# connectors_and_power.net
KiCad netlist of a schematic drawn in Altium Designer
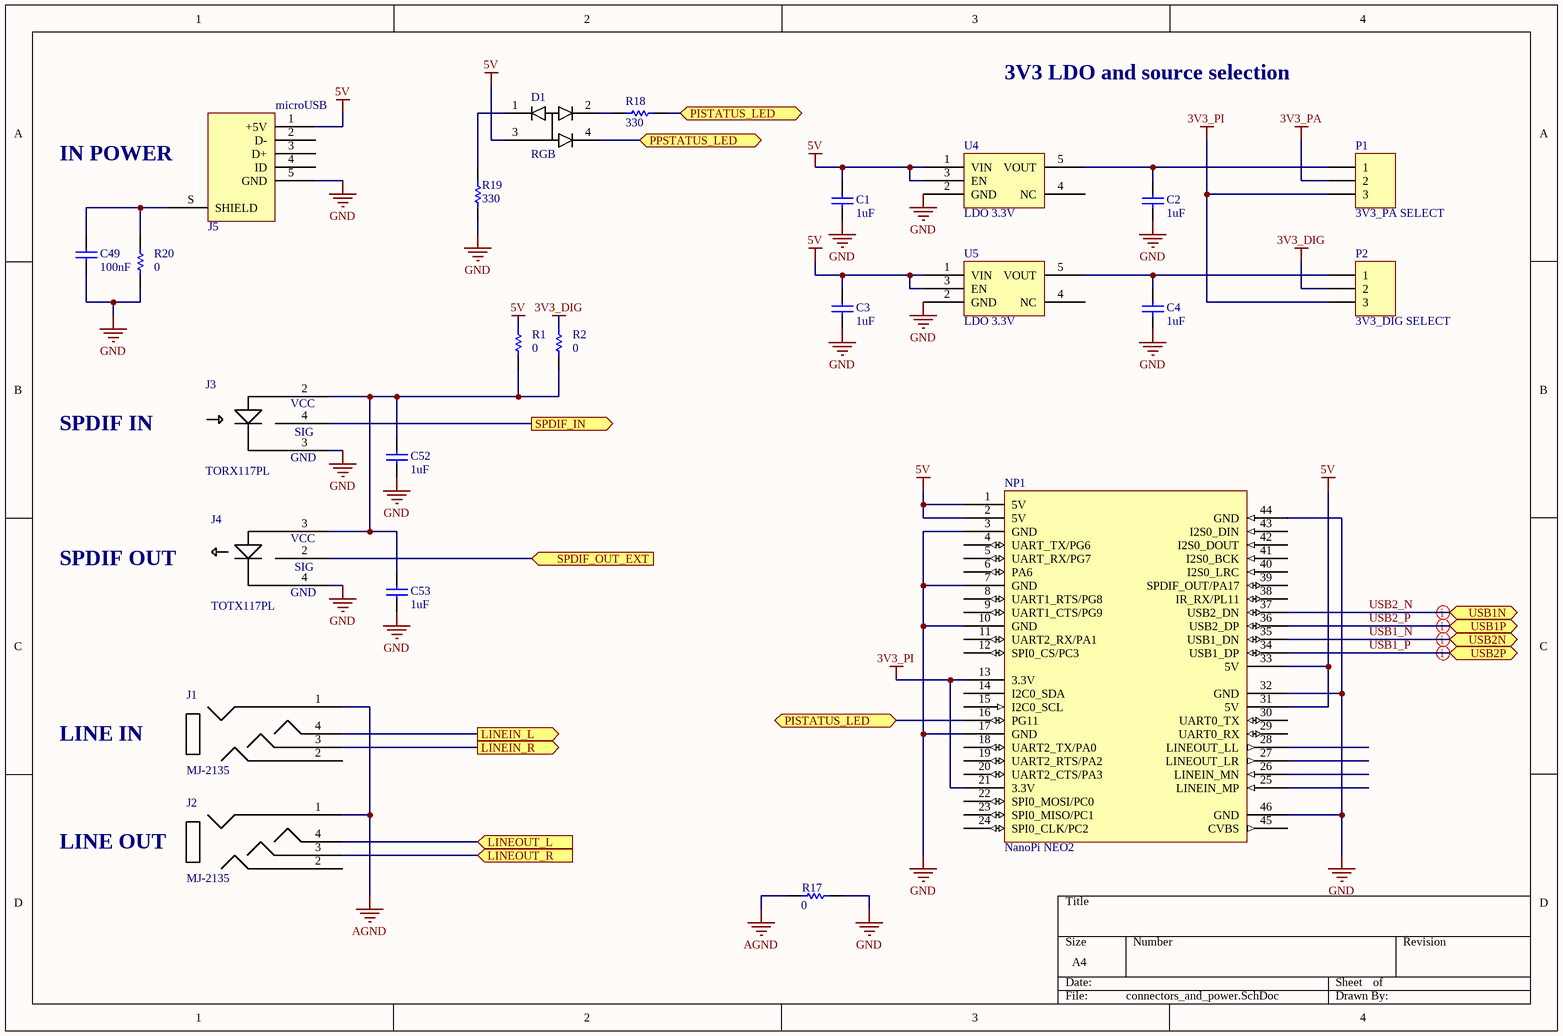
[diagram p0: connectors_and_power.SchDoc]

(export (version "E")
  (design (tool "Eeschema 10.0.6"))
  (components
    (comp (ref "C1")
      (value "1uF")
      (footprint "C_0402")
      (libsource (lib "Miscellaneous Devices") (part "Cap"))
    )
    (comp (ref "C2")
      (value "1uF")
      (footprint "C_0402")
      (libsource (lib "Miscellaneous Devices") (part "Cap"))
    )
    (comp (ref "C3")
      (value "1uF")
      (footprint "C_0402")
      (libsource (lib "Miscellaneous Devices") (part "Cap"))
    )
    (comp (ref "C4")
      (value "1uF")
      (footprint "C_0402")
      (libsource (lib "Miscellaneous Devices") (part "Cap"))
    )
    (comp (ref "C49")
      (value "100nF")
      (footprint "C_0402")
      (libsource (lib "Miscellaneous Devices") (part "Cap"))
    )
    (comp (ref "C52")
      (value "1uF")
      (footprint "C_0402")
      (libsource (lib "Miscellaneous Devices") (part "Cap"))
    )
    (comp (ref "C53")
      (value "1uF")
      (footprint "C_0402")
      (libsource (lib "Miscellaneous Devices") (part "Cap"))
    )
    (comp (ref "D1") (value "RGB") (footprint "RGB") (libsource (lib "Active Components") (part "RGB")))
    (comp (ref "J1")
      (value "MJ-2135")
      (footprint "audio jack")
      (description "3.5mm Audio jack")
      (libsource (lib "Connectors") (part "MJ-2135"))
    )
    (comp (ref "J2")
      (value "MJ-2135")
      (footprint "audio jack")
      (description "3.5mm Audio jack")
      (libsource (lib "Connectors") (part "MJ-2135"))
    )
    (comp (ref "J3")
      (value "TORX117PL")
      (footprint "TOXX177PL")
      (libsource (lib "Connectors") (part "TORX117PL"))
    )
    (comp (ref "J4")
      (value "TOTX117PL")
      (footprint "TOXX177PL")
      (libsource (lib "Connectors") (part "TOTX117PL"))
    )
    (comp (ref "J5")
      (value "Micro USB Jack")
      (footprint "microUSB")
      (description "Molex micro USB AB  47589-0001")
      (libsource (lib "Connectors") (part "Micro USB Jack"))
    )
    (comp (ref "NP1")
      (value "nanopi_neo2")
      (footprint "nanopi_neo2_dock")
      (description "Flipped NanoPi NEO2 dock")
      (libsource (lib "project_specific") (part "nanopi_neo2"))
    )
    (comp (ref "P1")
      (value "3V3_PA SELECT")
      (footprint "HDR1X3")
      (description "Header, 3-Pin")
      (fields (field (name "PUBLISHER") "Altium Limited"))
      (libsource (lib "Miscellaneous Connectors") (part "Header 3"))
    )
    (comp (ref "P2")
      (value "3V3_DIG SELECT")
      (footprint "HDR1X3")
      (description "Header, 3-Pin")
      (fields (field (name "PUBLISHER") "Altium Limited"))
      (libsource (lib "Miscellaneous Connectors") (part "Header 3"))
    )
    (comp (ref "R1")
      (value "0")
      (footprint "R_0402")
      (description "Resistor")
      (fields (field (name "Comment") "Res1"))
      (libsource (lib "Miscellaneous Devices") (part "Res1"))
    )
    (comp (ref "R2")
      (value "0")
      (footprint "R_0402")
      (description "Resistor")
      (fields (field (name "Comment") "Res1"))
      (libsource (lib "Miscellaneous Devices") (part "Res1"))
    )
    (comp (ref "R17")
      (value "0")
      (footprint "R_0402")
      (description "Resistor")
      (fields (field (name "Comment") "Res1"))
      (libsource (lib "Miscellaneous Devices") (part "Res1"))
    )
    (comp (ref "R18")
      (value "Res1")
      (footprint "R_0402")
      (description "Resistor")
      (fields (field (name "ALTIUM_UNNAMED_1") "330"))
      (libsource (lib "Miscellaneous Devices") (part "Res1"))
    )
    (comp (ref "R19")
      (value "Res1")
      (footprint "R_0402")
      (description "Resistor")
      (fields (field (name "ALTIUM_UNNAMED_1") "330"))
      (libsource (lib "Miscellaneous Devices") (part "Res1"))
    )
    (comp (ref "R20")
      (value "0")
      (footprint "R_0402")
      (description "Resistor")
      (fields (field (name "Comment") "Res1"))
      (libsource (lib "Miscellaneous Devices") (part "Res1"))
    )
    (comp (ref "U4")
      (value "LDO 3.3V")
      (footprint "SOT95P280X145-5N")
      (libsource (lib "Active Components") (part "LDO 3.3V"))
    )
    (comp (ref "U5")
      (value "LDO 3.3V")
      (footprint "SOT95P280X145-5N")
      (libsource (lib "Active Components") (part "LDO 3.3V"))
    )
  )
  (nets
    (net (code "1") (name "/LINEIN_L") (class "Default")
      (node (ref "J1") (pin "4") (pinfunction "4_4") (pintype "passive"))
    )
    (net (code "2") (name "/LINEIN_R") (class "Default")
      (node (ref "J1") (pin "3") (pinfunction "3_3") (pintype "passive"))
    )
    (net (code "3") (name "/LINEOUT_L") (class "Default")
      (node (ref "J2") (pin "4") (pinfunction "4_4") (pintype "passive"))
    )
    (net (code "4") (name "/LINEOUT_R") (class "Default")
      (node (ref "J2") (pin "3") (pinfunction "3_3") (pintype "passive"))
    )
    (net (code "5") (name "/PISTATUS_LED") (class "Default")
      (node (ref "NP1") (pin "16") (pinfunction "PG11_16") (pintype "bidirectional"))
      (node (ref "R18") (pin "1") (pinfunction "1_1") (pintype "passive"))
    )
    (net (code "6") (name "/PPSTATUS_LED") (class "Default")
      (node (ref "D1") (pin "4") (pinfunction "BLUE_4") (pintype "passive"))
    )
    (net (code "7") (name "/SPDIF_IN") (class "Default")
      (node (ref "J3") (pin "4") (pinfunction "SIG_4") (pintype "passive"))
    )
    (net (code "8") (name "/SPDIF_OUT_EXT") (class "Default")
      (node (ref "J4") (pin "2") (pinfunction "SIG_2") (pintype "passive"))
    )
    (net (code "9") (name "/USB1_N") (class "Default")
      (node (ref "NP1") (pin "35") (pinfunction "USB1_DN_35") (pintype "bidirectional"))
    )
    (net (code "10") (name "/USB1_P") (class "Default")
      (node (ref "NP1") (pin "34") (pinfunction "USB1_DP_34") (pintype "bidirectional"))
    )
    (net (code "11") (name "/USB2_N") (class "Default")
      (node (ref "NP1") (pin "37") (pinfunction "USB2_DN_37") (pintype "bidirectional"))
    )
    (net (code "12") (name "/USB2_P") (class "Default")
      (node (ref "NP1") (pin "36") (pinfunction "USB2_DP_36") (pintype "bidirectional"))
    )
    (net (code "13") (name "3V3_DIG") (class "Default")
      (node (ref "P2") (pin "2") (pinfunction "2_2") (pintype "passive"))
      (node (ref "R2") (pin "2") (pinfunction "2_2") (pintype "passive"))
    )
    (net (code "14") (name "3V3_PA") (class "Default")
      (node (ref "P1") (pin "2") (pinfunction "2_2") (pintype "passive"))
    )
    (net (code "15") (name "3V3_PI") (class "Default")
      (node (ref "NP1") (pin "13") (pinfunction "3.3V_13") (pintype "power_in"))
      (node (ref "NP1") (pin "21") (pinfunction "3.3V_21") (pintype "power_in"))
      (node (ref "P1") (pin "3") (pinfunction "3_3") (pintype "passive"))
      (node (ref "P2") (pin "3") (pinfunction "3_3") (pintype "passive"))
    )
    (net (code "16") (name "5V") (class "Default")
      (node (ref "C1") (pin "2") (pinfunction "2_2") (pintype "passive"))
      (node (ref "C3") (pin "2") (pinfunction "2_2") (pintype "passive"))
      (node (ref "D1") (pin "3") (pinfunction "ANODE_3") (pintype "passive"))
      (node (ref "J5") (pin "1") (pinfunction "+5V_1") (pintype "passive"))
      (node (ref "NP1") (pin "1") (pinfunction "5V_1") (pintype "power_in"))
      (node (ref "NP1") (pin "2") (pinfunction "5V_2") (pintype "power_in"))
      (node (ref "NP1") (pin "31") (pinfunction "5V_31") (pintype "power_in"))
      (node (ref "NP1") (pin "33") (pinfunction "5V_33") (pintype "power_in"))
      (node (ref "R1") (pin "2") (pinfunction "2_2") (pintype "passive"))
      (node (ref "U4") (pin "1") (pinfunction "VIN_1") (pintype "passive"))
      (node (ref "U4") (pin "3") (pinfunction "EN_3") (pintype "passive"))
      (node (ref "U5") (pin "1") (pinfunction "VIN_1") (pintype "passive"))
      (node (ref "U5") (pin "3") (pinfunction "EN_3") (pintype "passive"))
    )
    (net (code "17") (name "AGND") (class "Default")
      (node (ref "J1") (pin "1") (pinfunction "1_1") (pintype "passive"))
      (node (ref "J2") (pin "1") (pinfunction "1_1") (pintype "passive"))
      (node (ref "R17") (pin "2") (pinfunction "2_2") (pintype "passive"))
    )
    (net (code "18") (name "GND") (class "Default")
      (node (ref "C1") (pin "1") (pinfunction "1_1") (pintype "passive"))
      (node (ref "C2") (pin "1") (pinfunction "1_1") (pintype "passive"))
      (node (ref "C3") (pin "1") (pinfunction "1_1") (pintype "passive"))
      (node (ref "C4") (pin "1") (pinfunction "1_1") (pintype "passive"))
      (node (ref "C49") (pin "1") (pinfunction "1_1") (pintype "passive"))
      (node (ref "C52") (pin "1") (pinfunction "1_1") (pintype "passive"))
      (node (ref "C53") (pin "1") (pinfunction "1_1") (pintype "passive"))
      (node (ref "J3") (pin "3") (pinfunction "GND_3") (pintype "passive"))
      (node (ref "J4") (pin "4") (pinfunction "GND_4") (pintype "passive"))
      (node (ref "J5") (pin "5") (pinfunction "GND_5") (pintype "passive"))
      (node (ref "NP1") (pin "10") (pinfunction "GND_10") (pintype "power_in"))
      (node (ref "NP1") (pin "17") (pinfunction "GND_17") (pintype "power_in"))
      (node (ref "NP1") (pin "3") (pinfunction "GND_3") (pintype "power_in"))
      (node (ref "NP1") (pin "32") (pinfunction "GND_32") (pintype "power_in"))
      (node (ref "NP1") (pin "44") (pinfunction "GND_44") (pintype "input"))
      (node (ref "NP1") (pin "46") (pinfunction "GND_46") (pintype "power_in"))
      (node (ref "NP1") (pin "7") (pinfunction "GND_7") (pintype "power_in"))
      (node (ref "R17") (pin "1") (pinfunction "1_1") (pintype "passive"))
      (node (ref "R19") (pin "1") (pinfunction "1_1") (pintype "passive"))
      (node (ref "R20") (pin "1") (pinfunction "1_1") (pintype "passive"))
      (node (ref "U4") (pin "2") (pinfunction "GND_2") (pintype "passive"))
      (node (ref "U5") (pin "2") (pinfunction "GND_2") (pintype "passive"))
    )
    (net (code "19") (name "Net-(D1-GREEN)") (class "Default")
      (node (ref "D1") (pin "2") (pinfunction "GREEN_2") (pintype "passive"))
      (node (ref "R18") (pin "2") (pinfunction "2_2") (pintype "passive"))
    )
    (net (code "20") (name "Net-(D1-RED)") (class "Default")
      (node (ref "D1") (pin "1") (pinfunction "RED_1") (pintype "passive"))
      (node (ref "R19") (pin "2") (pinfunction "2_2") (pintype "passive"))
    )
    (net (code "21") (name "Net-(J3-VCC)") (class "Default")
      (node (ref "C52") (pin "2") (pinfunction "2_2") (pintype "passive"))
      (node (ref "C53") (pin "2") (pinfunction "2_2") (pintype "passive"))
      (node (ref "J3") (pin "2") (pinfunction "VCC_2") (pintype "passive"))
      (node (ref "J4") (pin "3") (pinfunction "VCC_3") (pintype "passive"))
      (node (ref "R1") (pin "1") (pinfunction "1_1") (pintype "passive"))
      (node (ref "R2") (pin "1") (pinfunction "1_1") (pintype "passive"))
    )
    (net (code "22") (name "Net-(J5-SHIELD)") (class "Default")
      (node (ref "C49") (pin "2") (pinfunction "2_2") (pintype "passive"))
      (node (ref "J5") (pin "S") (pinfunction "SHIELD_S") (pintype "passive"))
      (node (ref "R20") (pin "2") (pinfunction "2_2") (pintype "passive"))
    )
    (net (code "23") (name "Net-(U4-VOUT)") (class "Default")
      (node (ref "C2") (pin "2") (pinfunction "2_2") (pintype "passive"))
      (node (ref "P1") (pin "1") (pinfunction "1_1") (pintype "passive"))
      (node (ref "U4") (pin "5") (pinfunction "VOUT_5") (pintype "passive"))
    )
    (net (code "24") (name "Net-(U5-VOUT)") (class "Default")
      (node (ref "C4") (pin "2") (pinfunction "2_2") (pintype "passive"))
      (node (ref "P2") (pin "1") (pinfunction "1_1") (pintype "passive"))
      (node (ref "U5") (pin "5") (pinfunction "VOUT_5") (pintype "passive"))
    )
    (net (code "25") (name "unconnected-(J1-Pad2)") (class "Default")
      (node (ref "J1") (pin "2") (pinfunction "2_2") (pintype "passive"))
    )
    (net (code "26") (name "unconnected-(J2-Pad2)") (class "Default")
      (node (ref "J2") (pin "2") (pinfunction "2_2") (pintype "passive"))
    )
    (net (code "27") (name "unconnected-(J5-D+-Pad3)") (class "Default")
      (node (ref "J5") (pin "3") (pinfunction "D+_3") (pintype "passive"))
    )
    (net (code "28") (name "unconnected-(J5-D--Pad2)") (class "Default")
      (node (ref "J5") (pin "2") (pinfunction "D-_2") (pintype "passive"))
    )
    (net (code "29") (name "unconnected-(J5-ID-Pad4)") (class "Default")
      (node (ref "J5") (pin "4") (pinfunction "ID_4") (pintype "passive"))
    )
    (net (code "30") (name "unconnected-(NP1-CVBS-Pad45)") (class "Default")
      (node (ref "NP1") (pin "45") (pinfunction "CVBS_45") (pintype "output"))
    )
    (net (code "31") (name "unconnected-(NP1-I2C0_SCL-Pad15)") (class "Default")
      (node (ref "NP1") (pin "15") (pinfunction "I2C0_SCL_15") (pintype "input"))
    )
    (net (code "32") (name "unconnected-(NP1-I2C0_SDA-Pad14)") (class "Default")
      (node (ref "NP1") (pin "14") (pinfunction "I2C0_SDA_14") (pintype "open_collector"))
    )
    (net (code "33") (name "unconnected-(NP1-I2S0_BCK-Pad41)") (class "Default")
      (node (ref "NP1") (pin "41") (pinfunction "I2S0_BCK_41") (pintype "input"))
    )
    (net (code "34") (name "unconnected-(NP1-I2S0_DIN-Pad43)") (class "Default")
      (node (ref "NP1") (pin "43") (pinfunction "I2S0_DIN_43") (pintype "input"))
    )
    (net (code "35") (name "unconnected-(NP1-I2S0_DOUT-Pad42)") (class "Default")
      (node (ref "NP1") (pin "42") (pinfunction "I2S0_DOUT_42") (pintype "input"))
    )
    (net (code "36") (name "unconnected-(NP1-I2S0_LRC-Pad40)") (class "Default")
      (node (ref "NP1") (pin "40") (pinfunction "I2S0_LRC_40") (pintype "input"))
    )
    (net (code "37") (name "unconnected-(NP1-IR_RX{slash}PL11-Pad38)") (class "Default")
      (node (ref "NP1") (pin "38") (pinfunction "IR_RX/PL11_38") (pintype "bidirectional"))
    )
    (net (code "38") (name "unconnected-(NP1-LINEIN_MN-Pad26)") (class "Default")
      (node (ref "NP1") (pin "26") (pinfunction "LINEIN_MN_26") (pintype "input"))
    )
    (net (code "39") (name "unconnected-(NP1-LINEIN_MP-Pad25)") (class "Default")
      (node (ref "NP1") (pin "25") (pinfunction "LINEIN_MP_25") (pintype "input"))
    )
    (net (code "40") (name "unconnected-(NP1-LINEOUT_LL-Pad28)") (class "Default")
      (node (ref "NP1") (pin "28") (pinfunction "LINEOUT_LL_28") (pintype "output"))
    )
    (net (code "41") (name "unconnected-(NP1-LINEOUT_LR-Pad27)") (class "Default")
      (node (ref "NP1") (pin "27") (pinfunction "LINEOUT_LR_27") (pintype "output"))
    )
    (net (code "42") (name "unconnected-(NP1-PA6-Pad6)") (class "Default")
      (node (ref "NP1") (pin "6") (pinfunction "PA6_6") (pintype "bidirectional"))
    )
    (net (code "43") (name "unconnected-(NP1-SPDIF_OUT{slash}PA17-Pad39)") (class "Default")
      (node (ref "NP1") (pin "39") (pinfunction "SPDIF_OUT/PA17_39") (pintype "bidirectional"))
    )
    (net (code "44") (name "unconnected-(NP1-SPI0_CLK{slash}PC2-Pad24)") (class "Default")
      (node (ref "NP1") (pin "24") (pinfunction "SPI0_CLK/PC2_24") (pintype "bidirectional"))
    )
    (net (code "45") (name "unconnected-(NP1-SPI0_CS{slash}PC3-Pad12)") (class "Default")
      (node (ref "NP1") (pin "12") (pinfunction "SPI0_CS/PC3_12") (pintype "bidirectional"))
    )
    (net (code "46") (name "unconnected-(NP1-SPI0_MISO{slash}PC1-Pad23)") (class "Default")
      (node (ref "NP1") (pin "23") (pinfunction "SPI0_MISO/PC1_23") (pintype "bidirectional"))
    )
    (net (code "47") (name "unconnected-(NP1-SPI0_MOSI{slash}PC0-Pad22)") (class "Default")
      (node (ref "NP1") (pin "22") (pinfunction "SPI0_MOSI/PC0_22") (pintype "bidirectional"))
    )
    (net (code "48") (name "unconnected-(NP1-UART0_RX-Pad29)") (class "Default")
      (node (ref "NP1") (pin "29") (pinfunction "UART0_RX_29") (pintype "bidirectional"))
    )
    (net (code "49") (name "unconnected-(NP1-UART0_TX-Pad30)") (class "Default")
      (node (ref "NP1") (pin "30") (pinfunction "UART0_TX_30") (pintype "bidirectional"))
    )
    (net (code "50") (name "unconnected-(NP1-UART1_CTS{slash}PG9-Pad9)") (class "Default")
      (node (ref "NP1") (pin "9") (pinfunction "UART1_CTS/PG9_9") (pintype "bidirectional"))
    )
    (net (code "51") (name "unconnected-(NP1-UART1_RTS{slash}PG8-Pad8)") (class "Default")
      (node (ref "NP1") (pin "8") (pinfunction "UART1_RTS/PG8_8") (pintype "bidirectional"))
    )
    (net (code "52") (name "unconnected-(NP1-UART2_CTS{slash}PA3-Pad20)") (class "Default")
      (node (ref "NP1") (pin "20") (pinfunction "UART2_CTS/PA3_20") (pintype "bidirectional"))
    )
    (net (code "53") (name "unconnected-(NP1-UART2_RTS{slash}PA2-Pad19)") (class "Default")
      (node (ref "NP1") (pin "19") (pinfunction "UART2_RTS/PA2_19") (pintype "bidirectional"))
    )
    (net (code "54") (name "unconnected-(NP1-UART2_RX{slash}PA1-Pad11)") (class "Default")
      (node (ref "NP1") (pin "11") (pinfunction "UART2_RX/PA1_11") (pintype "bidirectional"))
    )
    (net (code "55") (name "unconnected-(NP1-UART2_TX{slash}PA0-Pad18)") (class "Default")
      (node (ref "NP1") (pin "18") (pinfunction "UART2_TX/PA0_18") (pintype "bidirectional"))
    )
    (net (code "56") (name "unconnected-(NP1-UART_RX{slash}PG7-Pad5)") (class "Default")
      (node (ref "NP1") (pin "5") (pinfunction "UART_RX/PG7_5") (pintype "bidirectional"))
    )
    (net (code "57") (name "unconnected-(NP1-UART_TX{slash}PG6-Pad4)") (class "Default")
      (node (ref "NP1") (pin "4") (pinfunction "UART_TX/PG6_4") (pintype "bidirectional"))
    )
    (net (code "58") (name "unconnected-(U4-NC-Pad4)") (class "Default")
      (node (ref "U4") (pin "4") (pinfunction "NC_4") (pintype "passive"))
    )
    (net (code "59") (name "unconnected-(U5-NC-Pad4)") (class "Default")
      (node (ref "U5") (pin "4") (pinfunction "NC_4") (pintype "passive"))
    )
  )
)
